# 15_PushButtons.net
KiCad netlist of a schematic drawn in Altium Designer
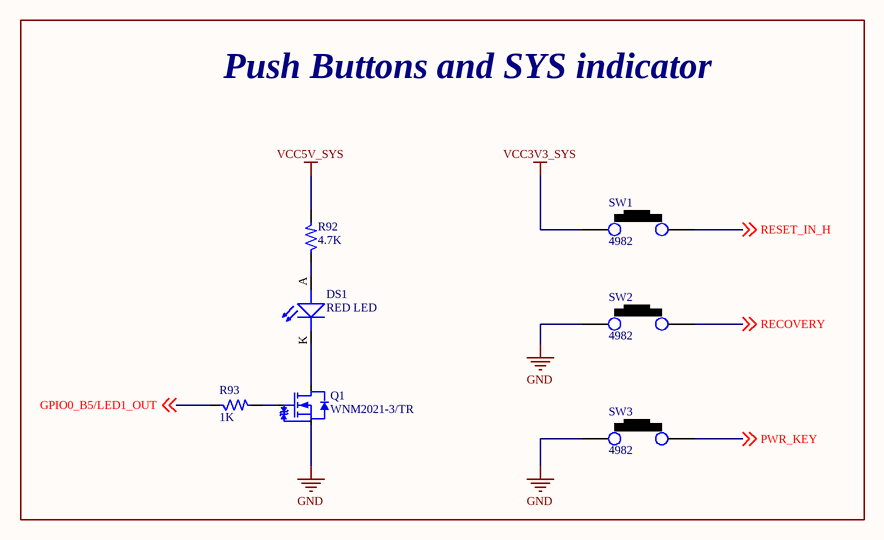
[diagram p0: [15] PushButtons.SchDoc]

(export (version "E")
  (design (tool "Eeschema 10.0.6"))
  (components
    (comp (ref "DS1")
      (value "RED LED")
      (footprint "LED_0805")
      (description "Red 631nm LED Indication - Discrete 2V 0805 (2012 Metric)")
      (fields
        (field (name "MANUFACTURER") "Vishay Lite-On")
        (field (name "MANUFACTURER PART NUMBER") "LTST-C171KRKT")
      )
      (libsource (lib "EsteemPCB_SOM_Course_intlib") (part "LED_RED-2V-20mA-0805"))
    )
    (comp (ref "Q1")
      (value "WNM2021-3/TR")
      (footprint "SOT-323-3")
      (description "N Channel 20V 820mA 850mV @ 250uA 310mΩ @ 550mA,4.5V 310mW SOT-323(SC-70) MOSFET RoHS")
      (fields (field (name "MANUFACTURER") "WILLSEMI(Will Semicon)"))
      (libsource (lib "EsteemPCB_SOM_Course_intlib") (part "MOSFET-N_20V-820mA-SOT-323"))
    )
    (comp (ref "R92")
      (value "4.7K")
      (footprint "RES_0201")
      (description "4.02 kOhms ±1% 0.05W, 1/20W Chip Resistor 0201 (0603 Metric) Thick Film")
      (fields
        (field (name "MANUFACTURER") "Yageo")
        (field (name "MANUFACTURER PART NUMBER") "RC0201FR-074K02L")
      )
      (libsource (lib "EsteemPCB_SOM_Course_intlib") (part "RES_4.7K-0.1W-1%-0201"))
    )
    (comp (ref "R93")
      (value "1K")
      (footprint "RES_0201")
      (description "1 kOhms ±1% 0.05W, 1/20W Chip Resistor 0201 (0603 Metric) Thick Film")
      (fields
        (field (name "MANUFACTURER") "Yageo")
        (field (name "MANUFACTURER PART NUMBER") "RC0201FR-071KL")
      )
      (libsource (lib "EsteemPCB_SOM_Course_intlib") (part "RES_1K-0.05W-1%-0201"))
    )
    (comp (ref "SW1")
      (value "4982")
      (footprint "SW_177_39.3X77.7_SMD")
      (description "Tactile Switch 3x4x2mm SMD 2-Pin")
      (fields (field (name "MANUFACTURER") "NA"))
      (libsource (lib "EsteemPCB_SOM_Course_intlib") (part "SW1_4982"))
    )
    (comp (ref "SW2")
      (value "4982")
      (footprint "SW_177_39.3X77.7_SMD")
      (description "Tactile Switch 3x4x2mm SMD 2-Pin")
      (fields (field (name "MANUFACTURER") "NA"))
      (libsource (lib "EsteemPCB_SOM_Course_intlib") (part "SW1_4982"))
    )
    (comp (ref "SW3")
      (value "4982")
      (footprint "SW_177_39.3X77.7_SMD")
      (description "Tactile Switch 3x4x2mm SMD 2-Pin")
      (fields (field (name "MANUFACTURER") "NA"))
      (libsource (lib "EsteemPCB_SOM_Course_intlib") (part "SW1_4982"))
    )
  )
  (nets
    (net (code "1") (name "GND") (class "Default")
      (node (ref "Q1") (pin "2") (pinfunction "S_2") (pintype "passive"))
      (node (ref "SW2") (pin "1") (pinfunction "1_1") (pintype "passive"))
      (node (ref "SW3") (pin "1") (pinfunction "1_1") (pintype "passive"))
    )
    (net (code "2") (name "GPIO0_B5{slash}LED1_OUT") (class "Default")
      (node (ref "R93") (pin "1") (pinfunction "1_1") (pintype "passive"))
    )
    (net (code "3") (name "Net-(DS1-ANODE)") (class "Default")
      (node (ref "DS1") (pin "A") (pinfunction "ANODE_A") (pintype "passive"))
      (node (ref "R92") (pin "1") (pinfunction "1_1") (pintype "passive"))
    )
    (net (code "4") (name "Net-(DS1-CATHODE)") (class "Default")
      (node (ref "DS1") (pin "K") (pinfunction "CATHODE_K") (pintype "passive"))
      (node (ref "Q1") (pin "3") (pinfunction "D_3") (pintype "passive"))
    )
    (net (code "5") (name "Net-(Q1-G)") (class "Default")
      (node (ref "Q1") (pin "1") (pinfunction "G_1") (pintype "passive"))
      (node (ref "R93") (pin "2") (pinfunction "2_2") (pintype "passive"))
    )
    (net (code "6") (name "PWR_KEY") (class "Default")
      (node (ref "SW3") (pin "2") (pinfunction "2_2") (pintype "passive"))
    )
    (net (code "7") (name "RECOVERY") (class "Default")
      (node (ref "SW2") (pin "2") (pinfunction "2_2") (pintype "passive"))
    )
    (net (code "8") (name "RESET_IN_H") (class "Default")
      (node (ref "SW1") (pin "2") (pinfunction "2_2") (pintype "passive"))
    )
    (net (code "9") (name "VCC3V3_SYS") (class "Default")
      (node (ref "SW1") (pin "1") (pinfunction "1_1") (pintype "passive"))
    )
    (net (code "10") (name "VCC5V_SYS") (class "Default")
      (node (ref "R92") (pin "2") (pinfunction "2_2") (pintype "passive"))
    )
  )
)
